# Transistor_Amp.net
KiCad netlist of a schematic drawn in Altium Designer
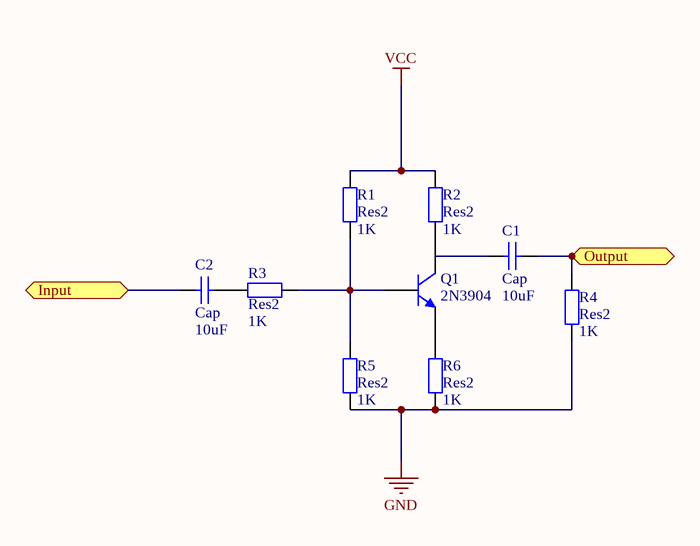
[diagram p0: Transistor_Amp.SchDoc]

(export (version "E")
  (design (tool "Eeschema 10.0.6"))
  (components
    (comp (ref "C1")
      (value "Cap")
      (footprint "RAD-0.3")
      (description "Capacitor")
      (fields (field (name "ALTIUM_VALUE") "10uF") (field (name "PUBLISHER") "Altium Limited"))
      (libsource (lib "Miscellaneous Devices") (part "Cap"))
    )
    (comp (ref "C2")
      (value "Cap")
      (footprint "RAD-0.3")
      (description "Capacitor")
      (fields (field (name "ALTIUM_VALUE") "10uF") (field (name "PUBLISHER") "Altium Limited"))
      (libsource (lib "Miscellaneous Devices") (part "Cap"))
    )
    (comp (ref "Q1")
      (value "2N3904")
      (footprint "TO-92A")
      (description "NPN General Purpose Amplifier")
      (fields (field (name "PUBLISHER") "Altium Limited"))
      (libsource (lib "Miscellaneous Devices") (part "2N3904"))
    )
    (comp (ref "R1")
      (value "Res2")
      (footprint "AXIAL-0.4")
      (description "Resistor")
      (fields (field (name "ALTIUM_VALUE") "1K") (field (name "PUBLISHER") "Altium Limited"))
      (libsource (lib "Miscellaneous Devices") (part "Res2"))
    )
    (comp (ref "R2")
      (value "Res2")
      (footprint "AXIAL-0.4")
      (description "Resistor")
      (fields (field (name "ALTIUM_VALUE") "1K") (field (name "PUBLISHER") "Altium Limited"))
      (libsource (lib "Miscellaneous Devices") (part "Res2"))
    )
    (comp (ref "R3")
      (value "Res2")
      (footprint "AXIAL-0.4")
      (description "Resistor")
      (fields (field (name "ALTIUM_VALUE") "1K") (field (name "PUBLISHER") "Altium Limited"))
      (libsource (lib "") (part "Res2_1"))
    )
    (comp (ref "R4")
      (value "Res2")
      (footprint "AXIAL-0.4")
      (description "Resistor")
      (fields (field (name "ALTIUM_VALUE") "1K") (field (name "PUBLISHER") "Altium Limited"))
      (libsource (lib "Miscellaneous Devices") (part "Res2"))
    )
    (comp (ref "R5")
      (value "Res2")
      (footprint "AXIAL-0.4")
      (description "Resistor")
      (fields (field (name "ALTIUM_VALUE") "1K") (field (name "PUBLISHER") "Altium Limited"))
      (libsource (lib "Miscellaneous Devices") (part "Res2"))
    )
    (comp (ref "R6")
      (value "Res2")
      (footprint "AXIAL-0.4")
      (description "Resistor")
      (fields (field (name "ALTIUM_VALUE") "1K") (field (name "PUBLISHER") "Altium Limited"))
      (libsource (lib "Miscellaneous Devices") (part "Res2"))
    )
  )
  (nets
    (net (code "1") (name "/Input") (class "Default")
      (node (ref "C2") (pin "1") (pinfunction "1_1") (pintype "passive"))
    )
    (net (code "2") (name "/Output") (class "Default")
      (node (ref "C1") (pin "2") (pinfunction "2_2") (pintype "passive"))
      (node (ref "R4") (pin "2") (pinfunction "2_2") (pintype "passive"))
    )
    (net (code "3") (name "GND") (class "Default")
      (node (ref "R4") (pin "1") (pinfunction "1_1") (pintype "passive"))
      (node (ref "R5") (pin "1") (pinfunction "1_1") (pintype "passive"))
      (node (ref "R6") (pin "1") (pinfunction "1_1") (pintype "passive"))
    )
    (net (code "4") (name "Net-(C2-Pad2)") (class "Default")
      (node (ref "C2") (pin "2") (pinfunction "2_2") (pintype "passive"))
      (node (ref "R3") (pin "1") (pinfunction "1_1") (pintype "passive"))
    )
    (net (code "5") (name "Net-(Q1-B)") (class "Default")
      (node (ref "Q1") (pin "2") (pinfunction "B_2") (pintype "passive"))
      (node (ref "R1") (pin "1") (pinfunction "1_1") (pintype "passive"))
      (node (ref "R3") (pin "2") (pinfunction "2_2") (pintype "passive"))
      (node (ref "R5") (pin "2") (pinfunction "2_2") (pintype "passive"))
    )
    (net (code "6") (name "Net-(Q1-C)") (class "Default")
      (node (ref "Q1") (pin "3") (pinfunction "C_3") (pintype "passive"))
      (node (ref "R2") (pin "1") (pinfunction "1_1") (pintype "passive"))
    )
    (net (code "7") (name "Net-(Q1-E)") (class "Default")
      (node (ref "Q1") (pin "1") (pinfunction "E_1") (pintype "passive"))
      (node (ref "R6") (pin "2") (pinfunction "2_2") (pintype "passive"))
    )
    (net (code "8") (name "VCC") (class "Default")
      (node (ref "R1") (pin "2") (pinfunction "2_2") (pintype "passive"))
      (node (ref "R2") (pin "2") (pinfunction "2_2") (pintype "passive"))
    )
    (net (code "9") (name "unconnected-(C1-Pad1)") (class "Default")
      (node (ref "C1") (pin "1") (pinfunction "1_1") (pintype "passive"))
    )
  )
)
